# PedalBoard.net
KiCad netlist of a schematic drawn in Altium Designer
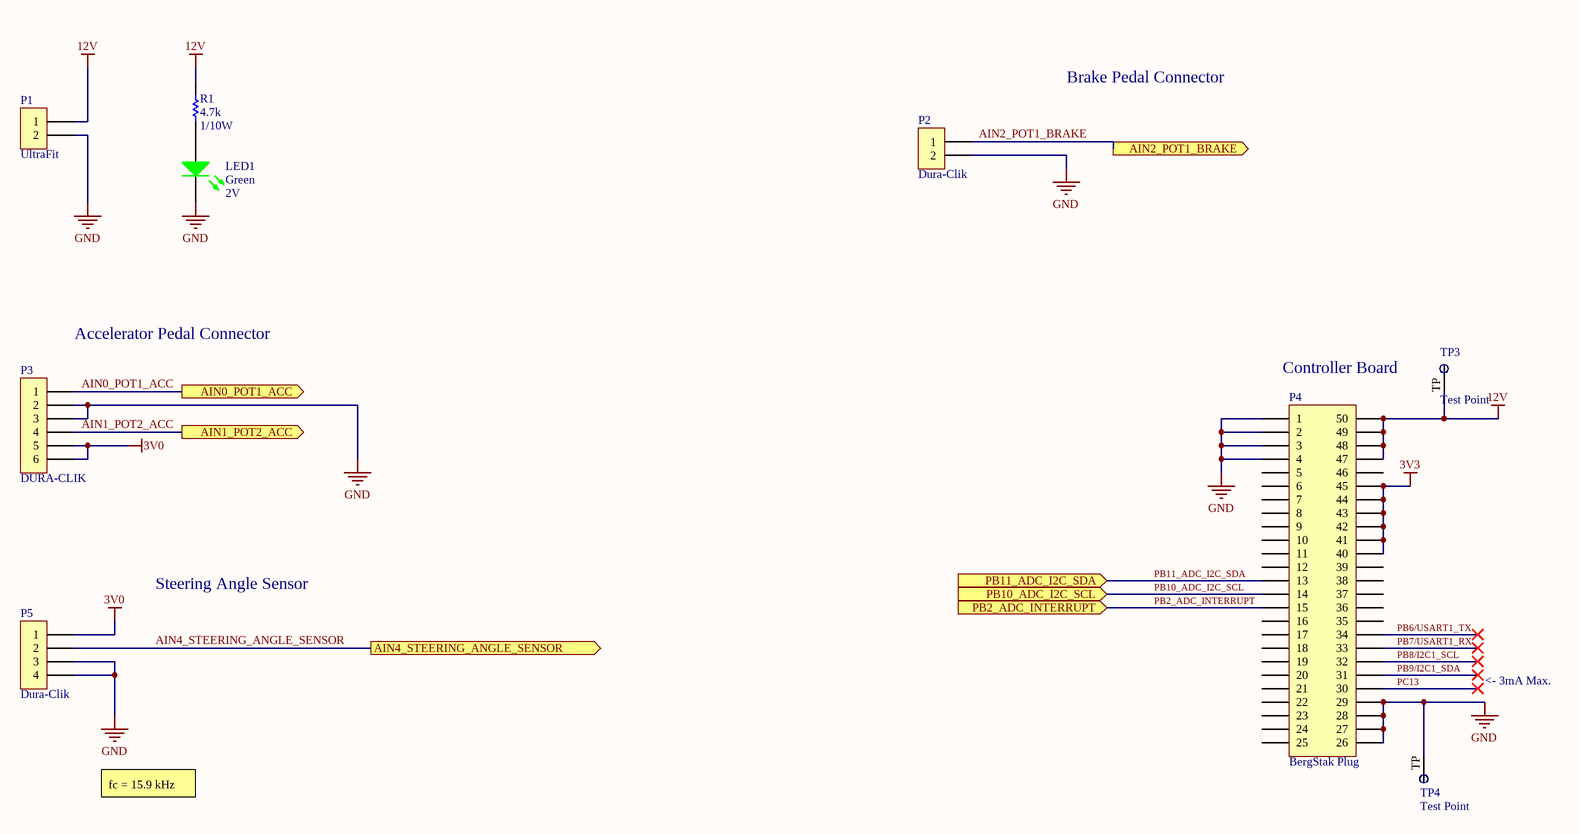
[diagram p0: PedalBoard.SchDoc]

(export (version "E")
  (design (tool "Eeschema 10.0.6"))
  (components
    (comp (ref "LED1")
      (value "LED GREEN CLEAR 2V 0603")
      (footprint "LED_0603")
      (description "Green 572nm LED Indication - Discrete 2V 0603 (1608 Metric)")
      (fields
        (field (name "MANUFACTURER") "Wurth Electronics Inc.")
        (field (name "MANUFACTURER PART NUMBER") "150060VS75000")
        (field (name "COLOR") "Green")
        (field (name "VOLTAGE - FORWARD (VF) (TYP)") "2V")
      )
      (libsource (lib "Schematic Diagrams") (part "LED GREEN CLEAR 2V 0603"))
    )
    (comp (ref "P1")
      (value "CONN 2POS ULTRA-FIT 0.138\"")
      (footprint "CONN, 2POS ULTRA-FIT")
      (description "2 Positions Header, Shrouded Connector 0.138\" (3.50mm) Through Hole Gold")
      (fields (field (name "VOLTAGE") "400V") (field (name "SERIES") "UltraFit"))
      (libsource (lib "Schematic Diagrams") (part "CONN 2POS ULTRA-FIT 0.138{dblquote}"))
    )
    (comp (ref "P2")
      (value "Dura-Clik")
      (footprint "CONN, 2POS Dura-Click Vertical")
      (description "2 Positions Header, Shrouded Connector 0.079\" (2.00mm) Surface Mount, Vertical Tin")
      (fields
        (field (name "MANUFACTURER") "Molex, LLC")
        (field (name "MANUFACTURER PART NUMBER") "5600200220")
      )
      (libsource (lib "Schematic Diagrams") (part "CONN 2POS DURA-CLIK 0.079{dblquote} VERT"))
    )
    (comp (ref "P3")
      (value "DURA-CLIK")
      (footprint "CONN, 6POS DURA-CLIK VERT")
      (description "6 Positions Header, Shrouded Connector 0.079\" (2.00mm) Surface Mount, Vertical Tin")
      (fields (field (name "MANUFACTURER") "Molex") (field (name "MANUFACTURER PART NUMBER") "5600200820"))
      (libsource (lib "Schematic Diagrams") (part "CONN 6POS DURA-CLIK 0.079{dblquote}"))
    )
    (comp (ref "P4")
      (value "CONN 50POS Bergstak Plug 0.02\"")
      (footprint "CONN, Bergstak 50 Pos Plug")
      (description "50 Position Connector Plug, Outer Shroud Contacts Surface Mount Gold")
      (fields (field (name "SERIES") "BergStak Plug"))
      (libsource (lib "Schematic Diagrams") (part "CONN 50POS Bergstak Plug 0.02{dblquote}"))
    )
    (comp (ref "P5")
      (value "Dura-Clik")
      (footprint "CONN, 4POS DURA-CLIK VERT")
      (description "4 Positions Header Connector 0.079\" (2.00mm) Surface Mount Tin")
      (fields
        (field (name "MANUFACTURER") "Molex, LLC")
        (field (name "MANUFACTURER PART NUMBER") "5600200420")
      )
      (libsource (lib "Schematic Diagrams") (part "CONN 4POS DURA-CLIK 0.079{dblquote}"))
    )
    (comp (ref "R1")
      (value "RES 4.7K OHM 1% 1/10W 0603")
      (footprint "RES, 0603")
      (description "4.7k Ohm ±1% 0.1W, 1/10W Chip Resistor 0603 (1608 Metric) Moisture Resistant Thick Film")
      (fields
        (field (name "TOLERANCE") "±1%")
        (field (name "RESISTANCE (OHMS)") "4.7k")
        (field (name "POWER (WATTS)") "1/10W")
      )
      (libsource (lib "Schematic Diagrams") (part "RES 4.7K OHM 1% 1/10W 0603"))
    )
    (comp (ref "TP3")
      (value "Test Point")
      (footprint "Test Point")
      (libsource (lib "Schematic Diagrams") (part "Test Point"))
    )
    (comp (ref "TP4")
      (value "Test Point")
      (footprint "Test Point")
      (libsource (lib "Schematic Diagrams") (part "Test Point"))
    )
  )
  (nets
    (net (code "1") (name "/AIN0_POT1_ACC") (class "Default")
      (node (ref "P3") (pin "1") (pinfunction "1_1") (pintype "passive"))
    )
    (net (code "2") (name "/AIN1_POT2_ACC") (class "Default")
      (node (ref "P3") (pin "4") (pinfunction "4_4") (pintype "passive"))
    )
    (net (code "3") (name "/AIN2_POT1_BRAKE") (class "Default")
      (node (ref "P2") (pin "1") (pinfunction "1_1") (pintype "passive"))
    )
    (net (code "4") (name "/AIN4_STEERING_ANGLE_SENSOR") (class "Default")
      (node (ref "P5") (pin "2") (pinfunction "2_2") (pintype "passive"))
    )
    (net (code "5") (name "/PB2_ADC_INTERRUPT") (class "Default")
      (node (ref "P4") (pin "15") (pinfunction "15_15") (pintype "passive"))
    )
    (net (code "6") (name "/PB6{slash}USART1_TX") (class "Default")
      (node (ref "P4") (pin "34") (pinfunction "34_34") (pintype "passive+no_connect"))
    )
    (net (code "7") (name "/PB7{slash}USART1_RX") (class "Default")
      (node (ref "P4") (pin "33") (pinfunction "33_33") (pintype "passive+no_connect"))
    )
    (net (code "8") (name "/PB8{slash}I2C1_SCL") (class "Default")
      (node (ref "P4") (pin "32") (pinfunction "32_32") (pintype "passive+no_connect"))
    )
    (net (code "9") (name "/PB9{slash}I2C1_SDA") (class "Default")
      (node (ref "P4") (pin "31") (pinfunction "31_31") (pintype "passive+no_connect"))
    )
    (net (code "10") (name "/PB10_ADC_I2C_SCL") (class "Default")
      (node (ref "P4") (pin "14") (pinfunction "14_14") (pintype "passive"))
    )
    (net (code "11") (name "/PB11_ADC_I2C_SDA") (class "Default")
      (node (ref "P4") (pin "13") (pinfunction "13_13") (pintype "passive"))
    )
    (net (code "12") (name "/PC13") (class "Default")
      (node (ref "P4") (pin "30") (pinfunction "30_30") (pintype "passive+no_connect"))
    )
    (net (code "13") (name "3V0") (class "Default")
      (node (ref "P3") (pin "5") (pinfunction "5_5") (pintype "passive"))
      (node (ref "P3") (pin "6") (pinfunction "6_6") (pintype "passive"))
      (node (ref "P5") (pin "1") (pinfunction "1_1") (pintype "passive"))
    )
    (net (code "14") (name "3V3") (class "Default")
      (node (ref "P4") (pin "40") (pinfunction "40_40") (pintype "passive"))
      (node (ref "P4") (pin "41") (pinfunction "41_41") (pintype "passive"))
      (node (ref "P4") (pin "42") (pinfunction "42_42") (pintype "passive"))
      (node (ref "P4") (pin "43") (pinfunction "43_43") (pintype "passive"))
      (node (ref "P4") (pin "44") (pinfunction "44_44") (pintype "passive"))
      (node (ref "P4") (pin "45") (pinfunction "45_45") (pintype "passive"))
    )
    (net (code "15") (name "12V") (class "Default")
      (node (ref "P1") (pin "1") (pinfunction "1_1") (pintype "passive"))
      (node (ref "P4") (pin "47") (pinfunction "47_47") (pintype "passive"))
      (node (ref "P4") (pin "48") (pinfunction "48_48") (pintype "passive"))
      (node (ref "P4") (pin "49") (pinfunction "49_49") (pintype "passive"))
      (node (ref "P4") (pin "50") (pinfunction "50_50") (pintype "passive"))
      (node (ref "R1") (pin "1") (pinfunction "1_1") (pintype "passive"))
      (node (ref "TP3") (pin "TP") (pinfunction "1_TP") (pintype "passive"))
    )
    (net (code "16") (name "GND") (class "Default")
      (node (ref "LED1") (pin "2") (pinfunction "K_2") (pintype "passive"))
      (node (ref "P1") (pin "2") (pinfunction "2_2") (pintype "passive"))
      (node (ref "P2") (pin "2") (pinfunction "2_2") (pintype "passive"))
      (node (ref "P3") (pin "2") (pinfunction "2_2") (pintype "passive"))
      (node (ref "P3") (pin "3") (pinfunction "3_3") (pintype "passive"))
      (node (ref "P4") (pin "1") (pinfunction "1_1") (pintype "passive"))
      (node (ref "P4") (pin "2") (pinfunction "2_2") (pintype "passive"))
      (node (ref "P4") (pin "26") (pinfunction "26_26") (pintype "passive"))
      (node (ref "P4") (pin "27") (pinfunction "27_27") (pintype "passive"))
      (node (ref "P4") (pin "28") (pinfunction "28_28") (pintype "passive"))
      (node (ref "P4") (pin "29") (pinfunction "29_29") (pintype "passive"))
      (node (ref "P4") (pin "3") (pinfunction "3_3") (pintype "passive"))
      (node (ref "P4") (pin "4") (pinfunction "4_4") (pintype "passive"))
      (node (ref "P5") (pin "3") (pinfunction "3_3") (pintype "passive"))
      (node (ref "P5") (pin "4") (pinfunction "4_4") (pintype "passive"))
      (node (ref "TP4") (pin "TP") (pinfunction "1_TP") (pintype "passive"))
    )
    (net (code "17") (name "Net-(LED1-A)") (class "Default")
      (node (ref "LED1") (pin "1") (pinfunction "A_1") (pintype "passive"))
      (node (ref "R1") (pin "2") (pinfunction "2_2") (pintype "passive"))
    )
    (net (code "18") (name "unconnected-(P4-Pad5)") (class "Default")
      (node (ref "P4") (pin "5") (pinfunction "5_5") (pintype "passive"))
    )
    (net (code "19") (name "unconnected-(P4-Pad6)") (class "Default")
      (node (ref "P4") (pin "6") (pinfunction "6_6") (pintype "passive"))
    )
    (net (code "20") (name "unconnected-(P4-Pad7)") (class "Default")
      (node (ref "P4") (pin "7") (pinfunction "7_7") (pintype "passive"))
    )
    (net (code "21") (name "unconnected-(P4-Pad8)") (class "Default")
      (node (ref "P4") (pin "8") (pinfunction "8_8") (pintype "passive"))
    )
    (net (code "22") (name "unconnected-(P4-Pad9)") (class "Default")
      (node (ref "P4") (pin "9") (pinfunction "9_9") (pintype "passive"))
    )
    (net (code "23") (name "unconnected-(P4-Pad10)") (class "Default")
      (node (ref "P4") (pin "10") (pinfunction "10_10") (pintype "passive"))
    )
    (net (code "24") (name "unconnected-(P4-Pad11)") (class "Default")
      (node (ref "P4") (pin "11") (pinfunction "11_11") (pintype "passive"))
    )
    (net (code "25") (name "unconnected-(P4-Pad12)") (class "Default")
      (node (ref "P4") (pin "12") (pinfunction "12_12") (pintype "passive"))
    )
    (net (code "26") (name "unconnected-(P4-Pad16)") (class "Default")
      (node (ref "P4") (pin "16") (pinfunction "16_16") (pintype "passive"))
    )
    (net (code "27") (name "unconnected-(P4-Pad17)") (class "Default")
      (node (ref "P4") (pin "17") (pinfunction "17_17") (pintype "passive"))
    )
    (net (code "28") (name "unconnected-(P4-Pad18)") (class "Default")
      (node (ref "P4") (pin "18") (pinfunction "18_18") (pintype "passive"))
    )
    (net (code "29") (name "unconnected-(P4-Pad19)") (class "Default")
      (node (ref "P4") (pin "19") (pinfunction "19_19") (pintype "passive"))
    )
    (net (code "30") (name "unconnected-(P4-Pad20)") (class "Default")
      (node (ref "P4") (pin "20") (pinfunction "20_20") (pintype "passive"))
    )
    (net (code "31") (name "unconnected-(P4-Pad21)") (class "Default")
      (node (ref "P4") (pin "21") (pinfunction "21_21") (pintype "passive"))
    )
    (net (code "32") (name "unconnected-(P4-Pad22)") (class "Default")
      (node (ref "P4") (pin "22") (pinfunction "22_22") (pintype "passive"))
    )
    (net (code "33") (name "unconnected-(P4-Pad23)") (class "Default")
      (node (ref "P4") (pin "23") (pinfunction "23_23") (pintype "passive"))
    )
    (net (code "34") (name "unconnected-(P4-Pad24)") (class "Default")
      (node (ref "P4") (pin "24") (pinfunction "24_24") (pintype "passive"))
    )
    (net (code "35") (name "unconnected-(P4-Pad25)") (class "Default")
      (node (ref "P4") (pin "25") (pinfunction "25_25") (pintype "passive"))
    )
    (net (code "36") (name "unconnected-(P4-Pad35)") (class "Default")
      (node (ref "P4") (pin "35") (pinfunction "35_35") (pintype "passive"))
    )
    (net (code "37") (name "unconnected-(P4-Pad36)") (class "Default")
      (node (ref "P4") (pin "36") (pinfunction "36_36") (pintype "passive"))
    )
    (net (code "38") (name "unconnected-(P4-Pad37)") (class "Default")
      (node (ref "P4") (pin "37") (pinfunction "37_37") (pintype "passive"))
    )
    (net (code "39") (name "unconnected-(P4-Pad38)") (class "Default")
      (node (ref "P4") (pin "38") (pinfunction "38_38") (pintype "passive"))
    )
    (net (code "40") (name "unconnected-(P4-Pad39)") (class "Default")
      (node (ref "P4") (pin "39") (pinfunction "39_39") (pintype "passive"))
    )
    (net (code "41") (name "unconnected-(P4-Pad46)") (class "Default")
      (node (ref "P4") (pin "46") (pinfunction "46_46") (pintype "passive"))
    )
  )
)
